# realParking.net
KiCad netlist of a schematic drawn in EAGLE
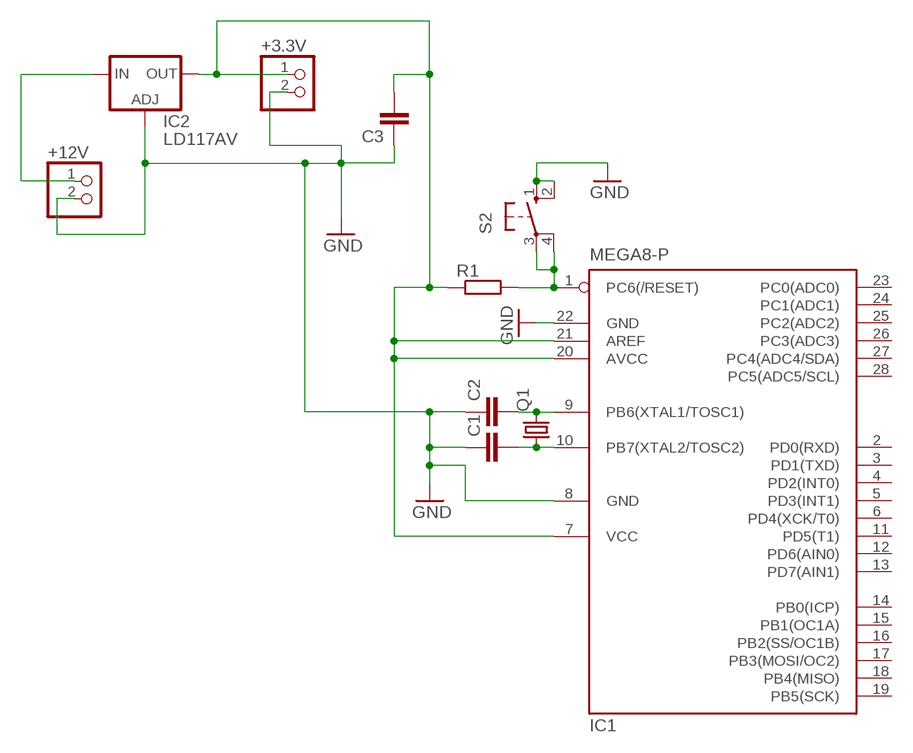
[diagram p0: schematic, sheet 1]

(export (version "E")
  (design (tool "Eeschema 10.0.6"))
  (components
    (comp (ref "+3.3V")
      (value "PINHD-1X2")
      (footprint "eagle-import:1X02")
      (libsource (lib "eagle-import") (part "PINHD-1X2"))
    )
    (comp (ref "+12V")
      (value "PINHD-1X2")
      (footprint "eagle-import:1X02")
      (libsource (lib "eagle-import") (part "PINHD-1X2"))
    )
    (comp (ref "C1")
      (value "C2,5-3")
      (footprint "eagle-import:C2.5-3")
      (libsource (lib "eagle-import") (part "C2,5-3"))
    )
    (comp (ref "C2")
      (value "C2,5-3")
      (footprint "eagle-import:C2.5-3")
      (libsource (lib "eagle-import") (part "C2,5-3"))
    )
    (comp (ref "C3")
      (value "C2,5-3")
      (footprint "eagle-import:C2.5-3")
      (libsource (lib "eagle-import") (part "C2,5-3"))
    )
    (comp (ref "IC1")
      (value "MEGA8-P")
      (footprint "eagle-import:DIL28-3")
      (libsource (lib "eagle-import") (part "MEGA8-P"))
    )
    (comp (ref "IC2")
      (value "LD117AV")
      (footprint "eagle-import:TO220L1")
      (libsource (lib "eagle-import") (part "LD117A?V"))
    )
    (comp (ref "Q1")
      (value "CRYSTALTC26V")
      (footprint "eagle-import:TC26V")
      (libsource (lib "eagle-import") (part "CRYSTALTC26V"))
    )
    (comp (ref "R1")
      (value "R-EU_0204/5")
      (footprint "eagle-import:0204_5")
      (libsource (lib "eagle-import") (part "R-EU_0204/5"))
    )
    (comp (ref "S2")
      (value "10-XX")
      (footprint "eagle-import:B3F-10XX")
      (fields (field (name "MPN") "B3F-1000"))
      (libsource (lib "eagle-import") (part "10-XX"))
    )
  )
  (nets
    (net (code "1") (name "GND") (class "Default")
      (node (ref "+12V") (pin "2") (pinfunction "2_2") (pintype "passive"))
      (node (ref "+3.3V") (pin "2") (pinfunction "2_2") (pintype "passive"))
      (node (ref "C1") (pin "1") (pinfunction "1_1") (pintype "passive"))
      (node (ref "C2") (pin "1") (pinfunction "1_1") (pintype "passive"))
      (node (ref "C3") (pin "1") (pinfunction "1_1") (pintype "passive"))
      (node (ref "IC1") (pin "22") (pinfunction "GND_22") (pintype "power_in"))
      (node (ref "IC1") (pin "8") (pinfunction "GND_8") (pintype "power_in"))
      (node (ref "IC2") (pin "1") (pinfunction "ADJ_1") (pintype "input"))
      (node (ref "S2") (pin "1") (pinfunction "S_1") (pintype "passive"))
      (node (ref "S2") (pin "2") (pinfunction "S1_2") (pintype "passive"))
    )
    (net (code "2") (name "Net-(IC1-AREF)") (class "Default")
      (node (ref "+3.3V") (pin "1") (pinfunction "1_1") (pintype "passive"))
      (node (ref "C3") (pin "2") (pinfunction "2_2") (pintype "passive"))
      (node (ref "IC1") (pin "20") (pinfunction "AVCC_20") (pintype "power_in"))
      (node (ref "IC1") (pin "21") (pinfunction "AREF_21") (pintype "passive"))
      (node (ref "IC1") (pin "7") (pinfunction "VCC_7") (pintype "power_in"))
      (node (ref "IC2") (pin "2") (pinfunction "OUT_2") (pintype "passive"))
      (node (ref "R1") (pin "1") (pinfunction "1_1") (pintype "passive"))
    )
    (net (code "3") (name "Net-(IC1-PB6(XTAL1{slash}TOSC1))") (class "Default")
      (node (ref "C2") (pin "2") (pinfunction "2_2") (pintype "passive"))
      (node (ref "IC1") (pin "9") (pinfunction "PB6(XTAL1/TOSC1)_9") (pintype "bidirectional"))
      (node (ref "Q1") (pin "2") (pinfunction "2_2") (pintype "passive"))
    )
    (net (code "4") (name "Net-(IC1-PB7(XTAL2{slash}TOSC2))") (class "Default")
      (node (ref "C1") (pin "2") (pinfunction "2_2") (pintype "passive"))
      (node (ref "IC1") (pin "10") (pinfunction "PB7(XTAL2/TOSC2)_10") (pintype "bidirectional"))
      (node (ref "Q1") (pin "1") (pinfunction "1_1") (pintype "passive"))
    )
    (net (code "5") (name "Net-(IC1-PC6({slash}RESET))") (class "Default")
      (node (ref "IC1") (pin "1") (pinfunction "PC6(/RESET)_1") (pintype "bidirectional"))
      (node (ref "R1") (pin "2") (pinfunction "2_2") (pintype "passive"))
      (node (ref "S2") (pin "3") (pinfunction "P_3") (pintype "passive"))
      (node (ref "S2") (pin "4") (pinfunction "P1_4") (pintype "passive"))
    )
    (net (code "6") (name "Net-(IC2-IN)") (class "Default")
      (node (ref "+12V") (pin "1") (pinfunction "1_1") (pintype "passive"))
      (node (ref "IC2") (pin "3") (pinfunction "IN_3") (pintype "input"))
    )
    (net (code "7") (name "unconnected-(IC1-PB0(ICP)-Pad14)") (class "Default")
      (node (ref "IC1") (pin "14") (pinfunction "PB0(ICP)_14") (pintype "bidirectional"))
    )
    (net (code "8") (name "unconnected-(IC1-PB1(OC1A)-Pad15)") (class "Default")
      (node (ref "IC1") (pin "15") (pinfunction "PB1(OC1A)_15") (pintype "bidirectional"))
    )
    (net (code "9") (name "unconnected-(IC1-PB2(SS{slash}OC1B)-Pad16)") (class "Default")
      (node (ref "IC1") (pin "16") (pinfunction "PB2(SS/OC1B)_16") (pintype "bidirectional"))
    )
    (net (code "10") (name "unconnected-(IC1-PB3(MOSI{slash}OC2)-Pad17)") (class "Default")
      (node (ref "IC1") (pin "17") (pinfunction "PB3(MOSI/OC2)_17") (pintype "bidirectional"))
    )
    (net (code "11") (name "unconnected-(IC1-PB4(MISO)-Pad18)") (class "Default")
      (node (ref "IC1") (pin "18") (pinfunction "PB4(MISO)_18") (pintype "bidirectional"))
    )
    (net (code "12") (name "unconnected-(IC1-PB5(SCK)-Pad19)") (class "Default")
      (node (ref "IC1") (pin "19") (pinfunction "PB5(SCK)_19") (pintype "bidirectional"))
    )
    (net (code "13") (name "unconnected-(IC1-PC0(ADC0)-Pad23)") (class "Default")
      (node (ref "IC1") (pin "23") (pinfunction "PC0(ADC0)_23") (pintype "bidirectional"))
    )
    (net (code "14") (name "unconnected-(IC1-PC1(ADC1)-Pad24)") (class "Default")
      (node (ref "IC1") (pin "24") (pinfunction "PC1(ADC1)_24") (pintype "bidirectional"))
    )
    (net (code "15") (name "unconnected-(IC1-PC2(ADC2)-Pad25)") (class "Default")
      (node (ref "IC1") (pin "25") (pinfunction "PC2(ADC2)_25") (pintype "bidirectional"))
    )
    (net (code "16") (name "unconnected-(IC1-PC3(ADC3)-Pad26)") (class "Default")
      (node (ref "IC1") (pin "26") (pinfunction "PC3(ADC3)_26") (pintype "bidirectional"))
    )
    (net (code "17") (name "unconnected-(IC1-PC4(ADC4{slash}SDA)-Pad27)") (class "Default")
      (node (ref "IC1") (pin "27") (pinfunction "PC4(ADC4/SDA)_27") (pintype "bidirectional"))
    )
    (net (code "18") (name "unconnected-(IC1-PC5(ADC5{slash}SCL)-Pad28)") (class "Default")
      (node (ref "IC1") (pin "28") (pinfunction "PC5(ADC5/SCL)_28") (pintype "bidirectional"))
    )
    (net (code "19") (name "unconnected-(IC1-PD0(RXD)-Pad2)") (class "Default")
      (node (ref "IC1") (pin "2") (pinfunction "PD0(RXD)_2") (pintype "bidirectional"))
    )
    (net (code "20") (name "unconnected-(IC1-PD1(TXD)-Pad3)") (class "Default")
      (node (ref "IC1") (pin "3") (pinfunction "PD1(TXD)_3") (pintype "bidirectional"))
    )
    (net (code "21") (name "unconnected-(IC1-PD2(INT0)-Pad4)") (class "Default")
      (node (ref "IC1") (pin "4") (pinfunction "PD2(INT0)_4") (pintype "bidirectional"))
    )
    (net (code "22") (name "unconnected-(IC1-PD3(INT1)-Pad5)") (class "Default")
      (node (ref "IC1") (pin "5") (pinfunction "PD3(INT1)_5") (pintype "bidirectional"))
    )
    (net (code "23") (name "unconnected-(IC1-PD4(XCK{slash}T0)-Pad6)") (class "Default")
      (node (ref "IC1") (pin "6") (pinfunction "PD4(XCK/T0)_6") (pintype "bidirectional"))
    )
    (net (code "24") (name "unconnected-(IC1-PD5(T1)-Pad11)") (class "Default")
      (node (ref "IC1") (pin "11") (pinfunction "PD5(T1)_11") (pintype "bidirectional"))
    )
    (net (code "25") (name "unconnected-(IC1-PD6(AIN0)-Pad12)") (class "Default")
      (node (ref "IC1") (pin "12") (pinfunction "PD6(AIN0)_12") (pintype "bidirectional"))
    )
    (net (code "26") (name "unconnected-(IC1-PD7(AIN1)-Pad13)") (class "Default")
      (node (ref "IC1") (pin "13") (pinfunction "PD7(AIN1)_13") (pintype "bidirectional"))
    )
  )
)
